# load-it.net
KiCad netlist of a schematic drawn in EAGLE
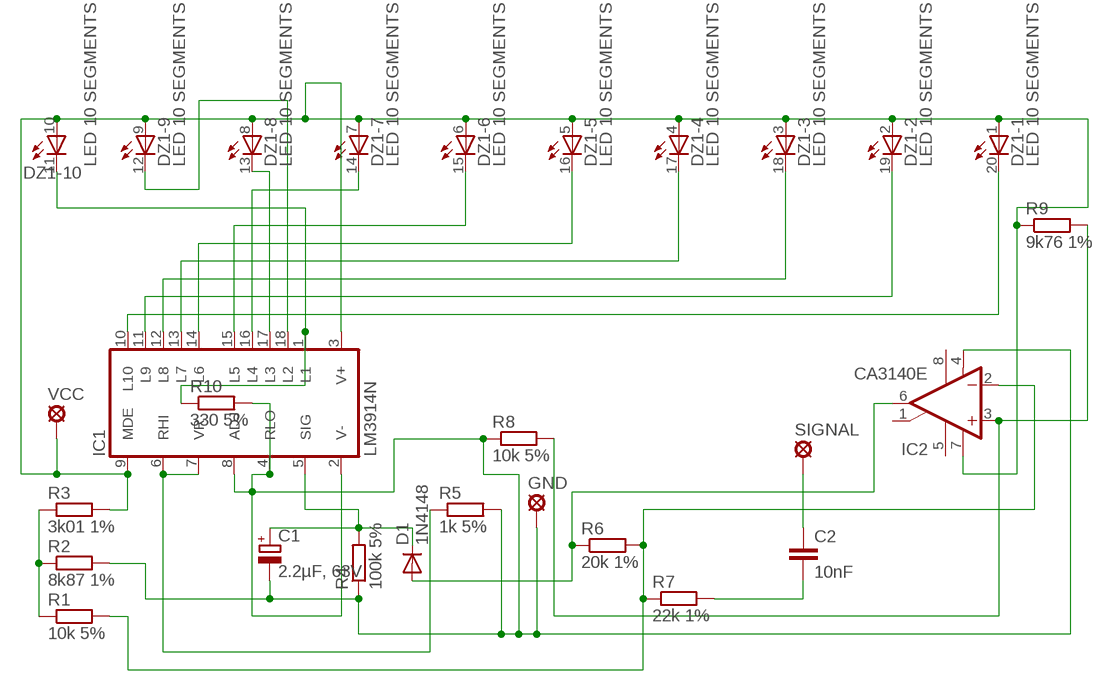
[diagram p0: schematic, sheet 1]

(export (version "E")
  (design (tool "Eeschema 10.0.6"))
  (components
    (comp (ref "C1")
      (value "2.2µF, 63V")
      (footprint "eagle-import:E5-6")
      (libsource (lib "eagle-import") (part "CPOL-EUE5-6"))
    )
    (comp (ref "C2")
      (value "10nF")
      (footprint "eagle-import:C2.5-2")
      (libsource (lib "eagle-import") (part "C2.5/2"))
    )
    (comp (ref "D1")
      (value "1N4148")
      (footprint "eagle-import:DO35-7")
      (libsource (lib "eagle-import") (part "1N4148DO35-7"))
    )
    (comp (ref "DZ1")
      (value "LED 10 SEGMENTS")
      (footprint "eagle-import:LB10")
      (libsource (lib "eagle-import") (part "LB10"))
    )
    (comp (ref "GND")
      (value "GND")
      (footprint "eagle-import:LSP10")
      (libsource (lib "eagle-import") (part "LSP10"))
    )
    (comp (ref "IC1")
      (value "LM3914N")
      (footprint "eagle-import:DIL18")
      (libsource (lib "eagle-import") (part "LM3914N"))
    )
    (comp (ref "IC2")
      (value "CA3140E")
      (footprint "eagle-import:DIL08")
      (libsource (lib "eagle-import") (part "CA3140N"))
    )
    (comp (ref "R1")
      (value "10k 5%")
      (footprint "eagle-import:0207_10")
      (libsource (lib "eagle-import") (part "R-EU_0207/10"))
    )
    (comp (ref "R2")
      (value "8k87 1%")
      (footprint "eagle-import:0207_10")
      (libsource (lib "eagle-import") (part "R-EU_0207/10"))
    )
    (comp (ref "R3")
      (value "3k01 1%")
      (footprint "eagle-import:0207_10")
      (libsource (lib "eagle-import") (part "R-EU_0207/10"))
    )
    (comp (ref "R4")
      (value "100k 5%")
      (footprint "eagle-import:0207_10")
      (libsource (lib "eagle-import") (part "R-EU_0207/10"))
    )
    (comp (ref "R5")
      (value "1k 5%")
      (footprint "eagle-import:0207_10")
      (libsource (lib "eagle-import") (part "R-EU_0207/10"))
    )
    (comp (ref "R6")
      (value "20k 1%")
      (footprint "eagle-import:0207_10")
      (libsource (lib "eagle-import") (part "R-EU_0207/10"))
    )
    (comp (ref "R7")
      (value "22k 1%")
      (footprint "eagle-import:0207_10")
      (libsource (lib "eagle-import") (part "R-EU_0207/10"))
    )
    (comp (ref "R8")
      (value "10k 5%")
      (footprint "eagle-import:0207_10")
      (libsource (lib "eagle-import") (part "R-EU_0207/10"))
    )
    (comp (ref "R9")
      (value "9k76 1%")
      (footprint "eagle-import:0207_10")
      (libsource (lib "eagle-import") (part "R-EU_0207/10"))
    )
    (comp (ref "R10")
      (value "330 5%")
      (footprint "eagle-import:0207_10")
      (libsource (lib "eagle-import") (part "R-EU_0207/10"))
    )
    (comp (ref "SIGNAL")
      (value "SG")
      (footprint "eagle-import:LSP10")
      (libsource (lib "eagle-import") (part "LSP10"))
    )
    (comp (ref "VCC")
      (value "VCC")
      (footprint "eagle-import:LSP10")
      (libsource (lib "eagle-import") (part "LSP10"))
    )
  )
  (nets
    (net (code "1") (name "Net-(C2-Pad1)") (class "Default")
      (node (ref "C2") (pin "1") (pinfunction "1_1") (pintype "passive"))
      (node (ref "SIGNAL") (pin "MP") (pinfunction "MP_MP") (pintype "passive"))
    )
    (net (code "2") (name "Net-(C2-Pad2)") (class "Default")
      (node (ref "C2") (pin "2") (pinfunction "2_2") (pintype "passive"))
      (node (ref "R7") (pin "2") (pinfunction "2_2") (pintype "passive"))
    )
    (net (code "3") (name "Net-(DZ1A-A)") (class "Default")
      (node (ref "DZ1") (pin "1") (pinfunction "A_1") (pintype "passive"))
      (node (ref "DZ1") (pin "10") (pinfunction "A_10") (pintype "passive"))
      (node (ref "DZ1") (pin "2") (pinfunction "A_2") (pintype "passive"))
      (node (ref "DZ1") (pin "3") (pinfunction "A_3") (pintype "passive"))
      (node (ref "DZ1") (pin "4") (pinfunction "A_4") (pintype "passive"))
      (node (ref "DZ1") (pin "5") (pinfunction "A_5") (pintype "passive"))
      (node (ref "DZ1") (pin "6") (pinfunction "A_6") (pintype "passive"))
      (node (ref "DZ1") (pin "7") (pinfunction "A_7") (pintype "passive"))
      (node (ref "DZ1") (pin "8") (pinfunction "A_8") (pintype "passive"))
      (node (ref "DZ1") (pin "9") (pinfunction "A_9") (pintype "passive"))
      (node (ref "IC1") (pin "3") (pinfunction "V+_3") (pintype "power_in"))
      (node (ref "IC1") (pin "9") (pinfunction "MDE_9") (pintype "input"))
      (node (ref "IC2") (pin "7") (pinfunction "V+_7") (pintype "power_in"))
      (node (ref "R3") (pin "2") (pinfunction "2_2") (pintype "passive"))
      (node (ref "R9") (pin "1") (pinfunction "1_1") (pintype "passive"))
      (node (ref "VCC") (pin "MP") (pinfunction "MP_MP") (pintype "passive"))
    )
    (net (code "4") (name "Net-(DZ1A-C)") (class "Default")
      (node (ref "DZ1") (pin "20") (pinfunction "C_20") (pintype "passive"))
      (node (ref "IC1") (pin "10") (pinfunction "L10_10") (pintype "output"))
    )
    (net (code "5") (name "Net-(DZ1B-C)") (class "Default")
      (node (ref "DZ1") (pin "11") (pinfunction "C_11") (pintype "passive"))
      (node (ref "IC1") (pin "1") (pinfunction "L1_1") (pintype "output"))
      (node (ref "R10") (pin "1") (pinfunction "1_1") (pintype "passive"))
    )
    (net (code "6") (name "Net-(DZ1C-C)") (class "Default")
      (node (ref "DZ1") (pin "19") (pinfunction "C_19") (pintype "passive"))
      (node (ref "IC1") (pin "11") (pinfunction "L9_11") (pintype "output"))
    )
    (net (code "7") (name "Net-(DZ1D-C)") (class "Default")
      (node (ref "DZ1") (pin "18") (pinfunction "C_18") (pintype "passive"))
      (node (ref "IC1") (pin "12") (pinfunction "L8_12") (pintype "output"))
    )
    (net (code "8") (name "Net-(DZ1E-C)") (class "Default")
      (node (ref "DZ1") (pin "17") (pinfunction "C_17") (pintype "passive"))
      (node (ref "IC1") (pin "13") (pinfunction "L7_13") (pintype "output"))
    )
    (net (code "9") (name "Net-(DZ1F-C)") (class "Default")
      (node (ref "DZ1") (pin "16") (pinfunction "C_16") (pintype "passive"))
      (node (ref "IC1") (pin "14") (pinfunction "L6_14") (pintype "output"))
    )
    (net (code "10") (name "Net-(DZ1G-C)") (class "Default")
      (node (ref "DZ1") (pin "15") (pinfunction "C_15") (pintype "passive"))
      (node (ref "IC1") (pin "15") (pinfunction "L5_15") (pintype "output"))
    )
    (net (code "11") (name "Net-(DZ1H-C)") (class "Default")
      (node (ref "DZ1") (pin "14") (pinfunction "C_14") (pintype "passive"))
      (node (ref "IC1") (pin "16") (pinfunction "L4_16") (pintype "output"))
    )
    (net (code "12") (name "Net-(DZ1I-C)") (class "Default")
      (node (ref "DZ1") (pin "13") (pinfunction "C_13") (pintype "passive"))
      (node (ref "IC1") (pin "17") (pinfunction "L3_17") (pintype "output"))
    )
    (net (code "13") (name "Net-(DZ1J-C)") (class "Default")
      (node (ref "DZ1") (pin "12") (pinfunction "C_12") (pintype "passive"))
      (node (ref "IC1") (pin "18") (pinfunction "L2_18") (pintype "output"))
    )
    (net (code "14") (name "Net-(IC1-ADJ)") (class "Default")
      (node (ref "C1") (pin "-") (pinfunction "-_-") (pintype "passive"))
      (node (ref "GND") (pin "MP") (pinfunction "MP_MP") (pintype "passive"))
      (node (ref "IC1") (pin "2") (pinfunction "V-_2") (pintype "power_in"))
      (node (ref "IC1") (pin "4") (pinfunction "RLO_4") (pintype "input"))
      (node (ref "IC1") (pin "8") (pinfunction "ADJ_8") (pintype "input"))
      (node (ref "IC2") (pin "4") (pinfunction "V-_4") (pintype "power_in"))
      (node (ref "R10") (pin "2") (pinfunction "2_2") (pintype "passive"))
      (node (ref "R2") (pin "2") (pinfunction "2_2") (pintype "passive"))
      (node (ref "R4") (pin "1") (pinfunction "1_1") (pintype "passive"))
      (node (ref "R5") (pin "2") (pinfunction "2_2") (pintype "passive"))
      (node (ref "R8") (pin "1") (pinfunction "1_1") (pintype "passive"))
    )
    (net (code "15") (name "Net-(IC1-RHI)") (class "Default")
      (node (ref "IC1") (pin "6") (pinfunction "RHI_6") (pintype "input"))
      (node (ref "IC1") (pin "7") (pinfunction "VR_7") (pintype "output"))
      (node (ref "R5") (pin "1") (pinfunction "1_1") (pintype "passive"))
    )
    (net (code "16") (name "Net-(IC1-SIG)") (class "Default")
      (node (ref "C1") (pin "+") (pinfunction "+_+") (pintype "passive"))
      (node (ref "D1") (pin "C") (pinfunction "C_C") (pintype "passive"))
      (node (ref "IC1") (pin "5") (pinfunction "SIG_5") (pintype "input"))
      (node (ref "R4") (pin "2") (pinfunction "2_2") (pintype "passive"))
    )
    (net (code "17") (name "Net-(IC2-+IN)") (class "Default")
      (node (ref "IC2") (pin "3") (pinfunction "+IN_3") (pintype "input"))
      (node (ref "R8") (pin "2") (pinfunction "2_2") (pintype "passive"))
      (node (ref "R9") (pin "2") (pinfunction "2_2") (pintype "passive"))
    )
    (net (code "18") (name "Net-(IC2--IN)") (class "Default")
      (node (ref "IC2") (pin "2") (pinfunction "-IN_2") (pintype "input"))
      (node (ref "R1") (pin "2") (pinfunction "2_2") (pintype "passive"))
      (node (ref "R6") (pin "2") (pinfunction "2_2") (pintype "passive"))
      (node (ref "R7") (pin "1") (pinfunction "1_1") (pintype "passive"))
    )
    (net (code "19") (name "Net-(IC2-OUT)") (class "Default")
      (node (ref "D1") (pin "A") (pinfunction "A_A") (pintype "passive"))
      (node (ref "IC2") (pin "6") (pinfunction "OUT_6") (pintype "output"))
      (node (ref "R6") (pin "1") (pinfunction "1_1") (pintype "passive"))
    )
    (net (code "20") (name "Net-(R1-Pad1)") (class "Default")
      (node (ref "R1") (pin "1") (pinfunction "1_1") (pintype "passive"))
      (node (ref "R2") (pin "1") (pinfunction "1_1") (pintype "passive"))
      (node (ref "R3") (pin "1") (pinfunction "1_1") (pintype "passive"))
    )
    (net (code "21") (name "unconnected-(IC2-CMP-Pad8)") (class "Default")
      (node (ref "IC2") (pin "8") (pinfunction "CMP_8") (pintype "passive"))
    )
    (net (code "22") (name "unconnected-(IC2-ON-Pad5)") (class "Default")
      (node (ref "IC2") (pin "5") (pinfunction "ON_5") (pintype "passive"))
    )
    (net (code "23") (name "unconnected-(IC2-ON{slash}CMP-Pad1)") (class "Default")
      (node (ref "IC2") (pin "1") (pinfunction "ON/CMP_1") (pintype "passive"))
    )
  )
)
